# fmradio.net
KiCad netlist of a schematic drawn in EAGLE
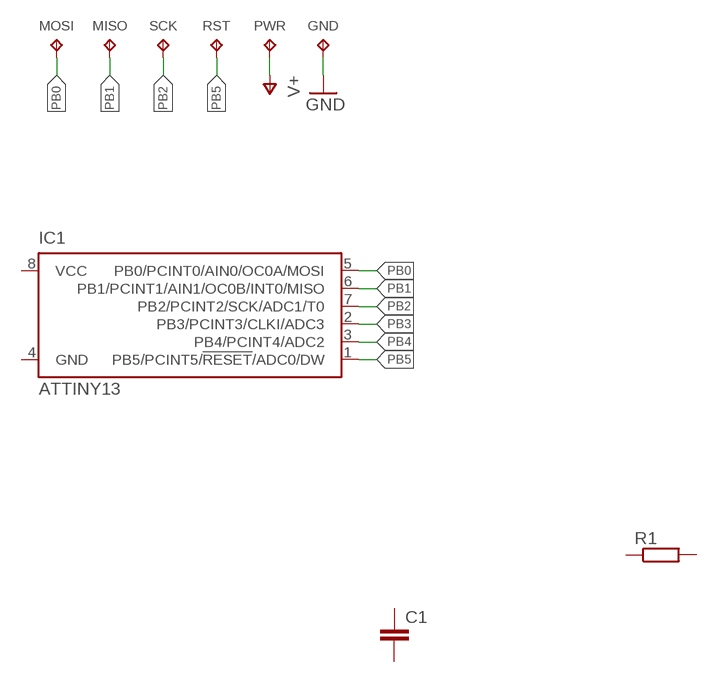
[diagram p0: schematic, sheet 1]
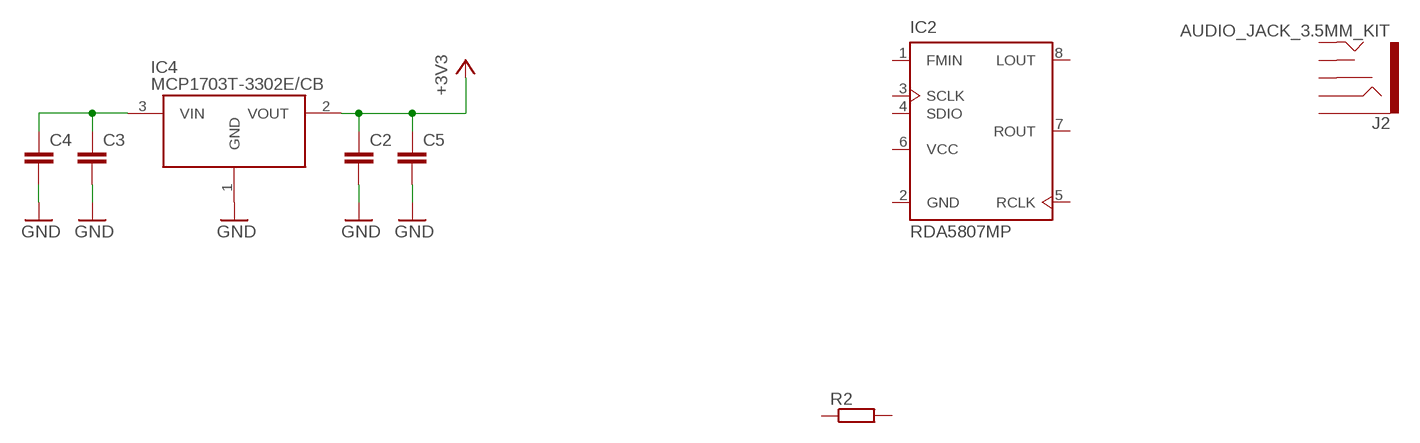
[diagram p1: schematic, sheet 2]
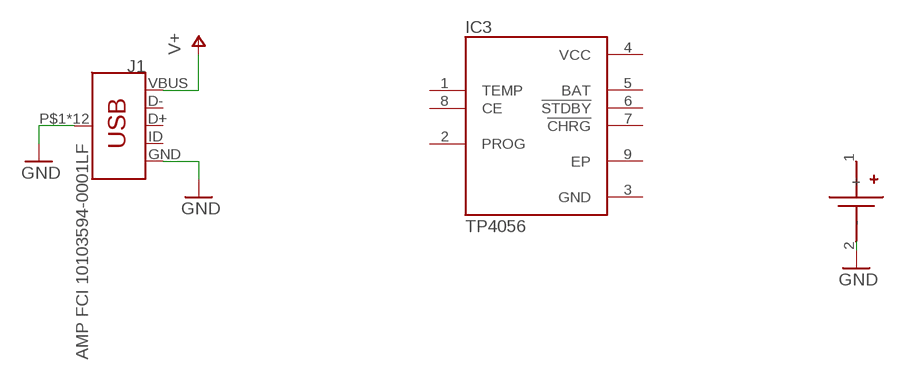
[diagram p2: schematic, sheet 3]

(export (version "E")
  (design (tool "Eeschema 10.0.6"))
  (components
    (comp (ref "C2")
      (value "C0603NOMINAL")
      (footprint "eagle-import:C0603_NOMINAL")
      (libsource (lib "eagle-import") (part "C0603NOMINAL"))
    )
    (comp (ref "C3")
      (value "C0603NOMINAL")
      (footprint "eagle-import:C0603_NOMINAL")
      (libsource (lib "eagle-import") (part "C0603NOMINAL"))
    )
    (comp (ref "C4")
      (value "C0603NOMINAL")
      (footprint "eagle-import:C0603_NOMINAL")
      (libsource (lib "eagle-import") (part "C0603NOMINAL"))
    )
    (comp (ref "C5")
      (value "C0603NOMINAL")
      (footprint "eagle-import:C0603_NOMINAL")
      (libsource (lib "eagle-import") (part "C0603NOMINAL"))
    )
    (comp (ref "IC2")
      (value "RDA5807MP")
      (footprint "eagle-import:8S1")
      (libsource (lib "eagle-import") (part "RDA5807MP"))
    )
    (comp (ref "IC4")
      (value "MCP1703T-3302E/CB")
      (footprint "eagle-import:SOT95P255X145-3N")
      (fields (field (name "MF") "Microchip"))
      (libsource (lib "eagle-import") (part "MCP1703T-3302E/CB"))
    )
    (comp (ref "J2")
      (value "AUDIO_JACK_3.5MM_KIT")
      (footprint "eagle-import:AUDIO-JACK-KIT")
      (libsource (lib "eagle-import") (part "AUDIO_JACK_3.5MM_KIT"))
    )
    (comp (ref "R2")
      (value "R0603NOMINAL")
      (footprint "eagle-import:R0603_NOMINAL")
      (libsource (lib "eagle-import") (part "R0603NOMINAL"))
    )
    (comp (ref "C1")
      (value "C0603NOMINAL")
      (footprint "eagle-import:C0603_NOMINAL")
      (libsource (lib "eagle-import") (part "C0603NOMINAL"))
    )
    (comp (ref "GND")
      (value "TPTP10R")
      (footprint "eagle-import:TP10R")
      (libsource (lib "eagle-import") (part "TPTP10R"))
    )
    (comp (ref "IC1")
      (value "ATTINY13")
      (footprint "eagle-import:8S1")
      (libsource (lib "eagle-import") (part "ATTINY13"))
    )
    (comp (ref "MISO")
      (value "TPTP10R")
      (footprint "eagle-import:TP10R")
      (libsource (lib "eagle-import") (part "TPTP10R"))
    )
    (comp (ref "MOSI")
      (value "TPTP10R")
      (footprint "eagle-import:TP10R")
      (libsource (lib "eagle-import") (part "TPTP10R"))
    )
    (comp (ref "PWR")
      (value "TPTP10R")
      (footprint "eagle-import:TP10R")
      (libsource (lib "eagle-import") (part "TPTP10R"))
    )
    (comp (ref "R1")
      (value "R0603NOMINAL")
      (footprint "eagle-import:R0603_NOMINAL")
      (libsource (lib "eagle-import") (part "R0603NOMINAL"))
    )
    (comp (ref "RST")
      (value "TPTP15R")
      (footprint "eagle-import:TP15R")
      (libsource (lib "eagle-import") (part "TPTP15R"))
    )
    (comp (ref "SCK")
      (value "TPTP10R")
      (footprint "eagle-import:TP10R")
      (libsource (lib "eagle-import") (part "TPTP10R"))
    )
    (comp (ref "IC3")
      (value "TP4056")
      (footprint "eagle-import:SOP127P600X175-9N")
      (fields (field (name "MF") "NanJing Top Power ASIC Corp."))
      (libsource (lib "eagle-import") (part "TP4056"))
    )
    (comp (ref "J1")
      (value "AMP FCI 10103594-0001LF")
      (footprint "eagle-import:USB-MICROB-PTH")
      (libsource (lib "eagle-import") (part "USB_MICRO-B_HALF_PTH"))
    )
    (comp (ref "U$1")
      (value "BLOSSOM-BLM-18650-1PCS")
      (footprint "eagle-import:BLOSSOM-BLM-18650-1PCS")
      (libsource (lib "eagle-import") (part "BLOSSOM-BLM-18650-1PCS"))
    )
  )
  (nets
    (net (code "1") (name "+3V3") (class "Default")
      (node (ref "C2") (pin "1") (pinfunction "1_1") (pintype "passive"))
      (node (ref "C5") (pin "1") (pinfunction "1_1") (pintype "passive"))
      (node (ref "IC4") (pin "2") (pinfunction "VOUT_2") (pintype "output"))
    )
    (net (code "2") (name "GND") (class "Default")
      (node (ref "C2") (pin "2") (pinfunction "2_2") (pintype "passive"))
      (node (ref "C3") (pin "2") (pinfunction "2_2") (pintype "passive"))
      (node (ref "C4") (pin "2") (pinfunction "2_2") (pintype "passive"))
      (node (ref "C5") (pin "2") (pinfunction "2_2") (pintype "passive"))
      (node (ref "GND") (pin "TP") (pinfunction "TP_TP") (pintype "input"))
      (node (ref "IC4") (pin "1") (pinfunction "GND_1") (pintype "power_in"))
      (node (ref "J1") (pin "GND") (pinfunction "GND_GND") (pintype "power_in"))
      (node (ref "J1") (pin "P$1") (pinfunction "SHIELD_P$1") (pintype "bidirectional"))
      (node (ref "J1") (pin "P$10") (pinfunction "SHIELD_P$10") (pintype "bidirectional"))
      (node (ref "J1") (pin "P$12") (pinfunction "SHIELD_P$12") (pintype "bidirectional"))
      (node (ref "J1") (pin "P$2") (pinfunction "SHIELD_P$2") (pintype "bidirectional"))
      (node (ref "J1") (pin "P$3") (pinfunction "SHIELD_P$3") (pintype "bidirectional"))
      (node (ref "J1") (pin "P$4") (pinfunction "SHIELD_P$4") (pintype "bidirectional"))
      (node (ref "J1") (pin "P$6") (pinfunction "SHIELD_P$6") (pintype "bidirectional"))
      (node (ref "J1") (pin "P$8") (pinfunction "SHIELD_P$8") (pintype "bidirectional"))
      (node (ref "J1") (pin "SHEILD2") (pinfunction "SHIELD_SHEILD2") (pintype "bidirectional"))
      (node (ref "J1") (pin "SHIELD") (pinfunction "SHIELD_SHIELD") (pintype "bidirectional"))
      (node (ref "J1") (pin "SHIELD3") (pinfunction "SHIELD_SHIELD3") (pintype "bidirectional"))
      (node (ref "J1") (pin "SHIELD4") (pinfunction "SHIELD_SHIELD4") (pintype "bidirectional"))
      (node (ref "U$1") (pin "2") (pinfunction "-_2") (pintype "bidirectional"))
    )
    (net (code "3") (name "Net-(IC4-VIN)") (class "Default")
      (node (ref "C3") (pin "1") (pinfunction "1_1") (pintype "passive"))
      (node (ref "C4") (pin "1") (pinfunction "1_1") (pintype "passive"))
      (node (ref "IC4") (pin "3") (pinfunction "VIN_3") (pintype "input"))
    )
    (net (code "4") (name "PB0") (class "Default")
      (node (ref "IC1") (pin "5") (pinfunction "PB0/PCINT0/AIN0/OC0A/MOSI_5") (pintype "bidirectional"))
      (node (ref "MOSI") (pin "TP") (pinfunction "TP_TP") (pintype "input"))
    )
    (net (code "5") (name "PB1") (class "Default")
      (node (ref "IC1") (pin "6") (pinfunction "PB1/PCINT1/AIN1/OC0B/INT0/MISO_6") (pintype "bidirectional"))
      (node (ref "MISO") (pin "TP") (pinfunction "TP_TP") (pintype "input"))
    )
    (net (code "6") (name "PB2") (class "Default")
      (node (ref "IC1") (pin "7") (pinfunction "PB2/PCINT2/SCK/ADC1/T0_7") (pintype "bidirectional"))
      (node (ref "SCK") (pin "TP") (pinfunction "TP_TP") (pintype "input"))
    )
    (net (code "7") (name "PB3") (class "Default")
      (node (ref "IC1") (pin "2") (pinfunction "PB3/PCINT3/CLKI/ADC3_2") (pintype "bidirectional"))
    )
    (net (code "8") (name "PB4") (class "Default")
      (node (ref "IC1") (pin "3") (pinfunction "PB4/PCINT4/ADC2_3") (pintype "bidirectional"))
    )
    (net (code "9") (name "PB5") (class "Default")
      (node (ref "IC1") (pin "1") (pinfunction "PB5/PCINT5/~{RESET}/ADC0/DW_1") (pintype "bidirectional"))
      (node (ref "RST") (pin "TP") (pinfunction "TP_TP") (pintype "input"))
    )
    (net (code "10") (name "V+") (class "Default")
      (node (ref "J1") (pin "VBUS") (pinfunction "VBUS_VBUS") (pintype "power_in"))
      (node (ref "PWR") (pin "TP") (pinfunction "TP_TP") (pintype "input"))
    )
    (net (code "11") (name "unconnected-(C1-Pad1)") (class "Default")
      (node (ref "C1") (pin "1") (pinfunction "1_1") (pintype "passive"))
    )
    (net (code "12") (name "unconnected-(C1-Pad2)") (class "Default")
      (node (ref "C1") (pin "2") (pinfunction "2_2") (pintype "passive"))
    )
    (net (code "13") (name "unconnected-(IC1-GND-Pad4)") (class "Default")
      (node (ref "IC1") (pin "4") (pinfunction "GND_4") (pintype "bidirectional"))
    )
    (net (code "14") (name "unconnected-(IC1-VCC-Pad8)") (class "Default")
      (node (ref "IC1") (pin "8") (pinfunction "VCC_8") (pintype "bidirectional"))
    )
    (net (code "15") (name "unconnected-(IC2-FMIN-Pad1)") (class "Default")
      (node (ref "IC2") (pin "1") (pinfunction "FMIN_1") (pintype "input"))
    )
    (net (code "16") (name "unconnected-(IC2-GND-Pad2)") (class "Default")
      (node (ref "IC2") (pin "2") (pinfunction "GND_2") (pintype "bidirectional"))
    )
    (net (code "17") (name "unconnected-(IC2-LOUT-Pad8)") (class "Default")
      (node (ref "IC2") (pin "8") (pinfunction "LOUT_8") (pintype "output"))
    )
    (net (code "18") (name "unconnected-(IC2-RCLK-Pad5)") (class "Default")
      (node (ref "IC2") (pin "5") (pinfunction "RCLK_5") (pintype "input"))
    )
    (net (code "19") (name "unconnected-(IC2-ROUT-Pad7)") (class "Default")
      (node (ref "IC2") (pin "7") (pinfunction "ROUT_7") (pintype "output"))
    )
    (net (code "20") (name "unconnected-(IC2-SCLK-Pad3)") (class "Default")
      (node (ref "IC2") (pin "3") (pinfunction "SCLK_3") (pintype "input"))
    )
    (net (code "21") (name "unconnected-(IC2-SDIO-Pad4)") (class "Default")
      (node (ref "IC2") (pin "4") (pinfunction "SDIO_4") (pintype "bidirectional"))
    )
    (net (code "22") (name "unconnected-(IC2-VCC-Pad6)") (class "Default")
      (node (ref "IC2") (pin "6") (pinfunction "VCC_6") (pintype "bidirectional"))
    )
    (net (code "23") (name "unconnected-(IC3-BAT-Pad5)") (class "Default")
      (node (ref "IC3") (pin "5") (pinfunction "BAT_5") (pintype "output"))
    )
    (net (code "24") (name "unconnected-(IC3-CE-Pad8)") (class "Default")
      (node (ref "IC3") (pin "8") (pinfunction "CE_8") (pintype "input"))
    )
    (net (code "25") (name "unconnected-(IC3-EP-Pad9)") (class "Default")
      (node (ref "IC3") (pin "9") (pinfunction "EP_9") (pintype "passive"))
    )
    (net (code "26") (name "unconnected-(IC3-GND-Pad3)") (class "Default")
      (node (ref "IC3") (pin "3") (pinfunction "GND_3") (pintype "bidirectional"))
    )
    (net (code "27") (name "unconnected-(IC3-PROG-Pad2)") (class "Default")
      (node (ref "IC3") (pin "2") (pinfunction "PROG_2") (pintype "bidirectional"))
    )
    (net (code "28") (name "unconnected-(IC3-TEMP-Pad1)") (class "Default")
      (node (ref "IC3") (pin "1") (pinfunction "TEMP_1") (pintype "input"))
    )
    (net (code "29") (name "unconnected-(IC3-VCC-Pad4)") (class "Default")
      (node (ref "IC3") (pin "4") (pinfunction "VCC_4") (pintype "bidirectional"))
    )
    (net (code "30") (name "unconnected-(IC3-~{CHRG}-Pad7)") (class "Default")
      (node (ref "IC3") (pin "7") (pinfunction "~{CHRG}_7") (pintype "output"))
    )
    (net (code "31") (name "unconnected-(IC3-~{STDBY}-Pad6)") (class "Default")
      (node (ref "IC3") (pin "6") (pinfunction "~{STDBY}_6") (pintype "output"))
    )
    (net (code "32") (name "unconnected-(J1-PadD+)") (class "Default")
      (node (ref "J1") (pin "D+") (pinfunction "D+_D+") (pintype "bidirectional"))
    )
    (net (code "33") (name "unconnected-(J1-PadD-)") (class "Default")
      (node (ref "J1") (pin "D-") (pinfunction "D-_D-") (pintype "bidirectional"))
    )
    (net (code "34") (name "unconnected-(J1-PadID)") (class "Default")
      (node (ref "J1") (pin "ID") (pinfunction "ID_ID") (pintype "bidirectional"))
    )
    (net (code "35") (name "unconnected-(J2-PadRING)") (class "Default")
      (node (ref "J2") (pin "RING") (pinfunction "RING_RING") (pintype "bidirectional"))
    )
    (net (code "36") (name "unconnected-(J2-PadRSH)") (class "Default")
      (node (ref "J2") (pin "RSH") (pinfunction "RSH_RSH") (pintype "bidirectional"))
    )
    (net (code "37") (name "unconnected-(J2-PadSLEEVE)") (class "Default")
      (node (ref "J2") (pin "SLEEVE") (pinfunction "SLEEVE_SLEEVE") (pintype "bidirectional"))
    )
    (net (code "38") (name "unconnected-(J2-PadTIP)") (class "Default")
      (node (ref "J2") (pin "TIP") (pinfunction "TIP_TIP") (pintype "bidirectional"))
    )
    (net (code "39") (name "unconnected-(J2-PadTSH)") (class "Default")
      (node (ref "J2") (pin "TSH") (pinfunction "TSH_TSH") (pintype "bidirectional"))
    )
    (net (code "40") (name "unconnected-(R1-Pad1)") (class "Default")
      (node (ref "R1") (pin "1") (pinfunction "1_1") (pintype "passive"))
    )
    (net (code "41") (name "unconnected-(R1-Pad2)") (class "Default")
      (node (ref "R1") (pin "2") (pinfunction "2_2") (pintype "passive"))
    )
    (net (code "42") (name "unconnected-(R2-Pad1)") (class "Default")
      (node (ref "R2") (pin "1") (pinfunction "1_1") (pintype "passive"))
    )
    (net (code "43") (name "unconnected-(R2-Pad2)") (class "Default")
      (node (ref "R2") (pin "2") (pinfunction "2_2") (pintype "passive"))
    )
    (net (code "44") (name "unconnected-(U$1-+-Pad1)") (class "Default")
      (node (ref "U$1") (pin "1") (pinfunction "+_1") (pintype "bidirectional"))
    )
  )
)
